# MCU1.net
KiCad netlist of a schematic drawn in Altium Designer
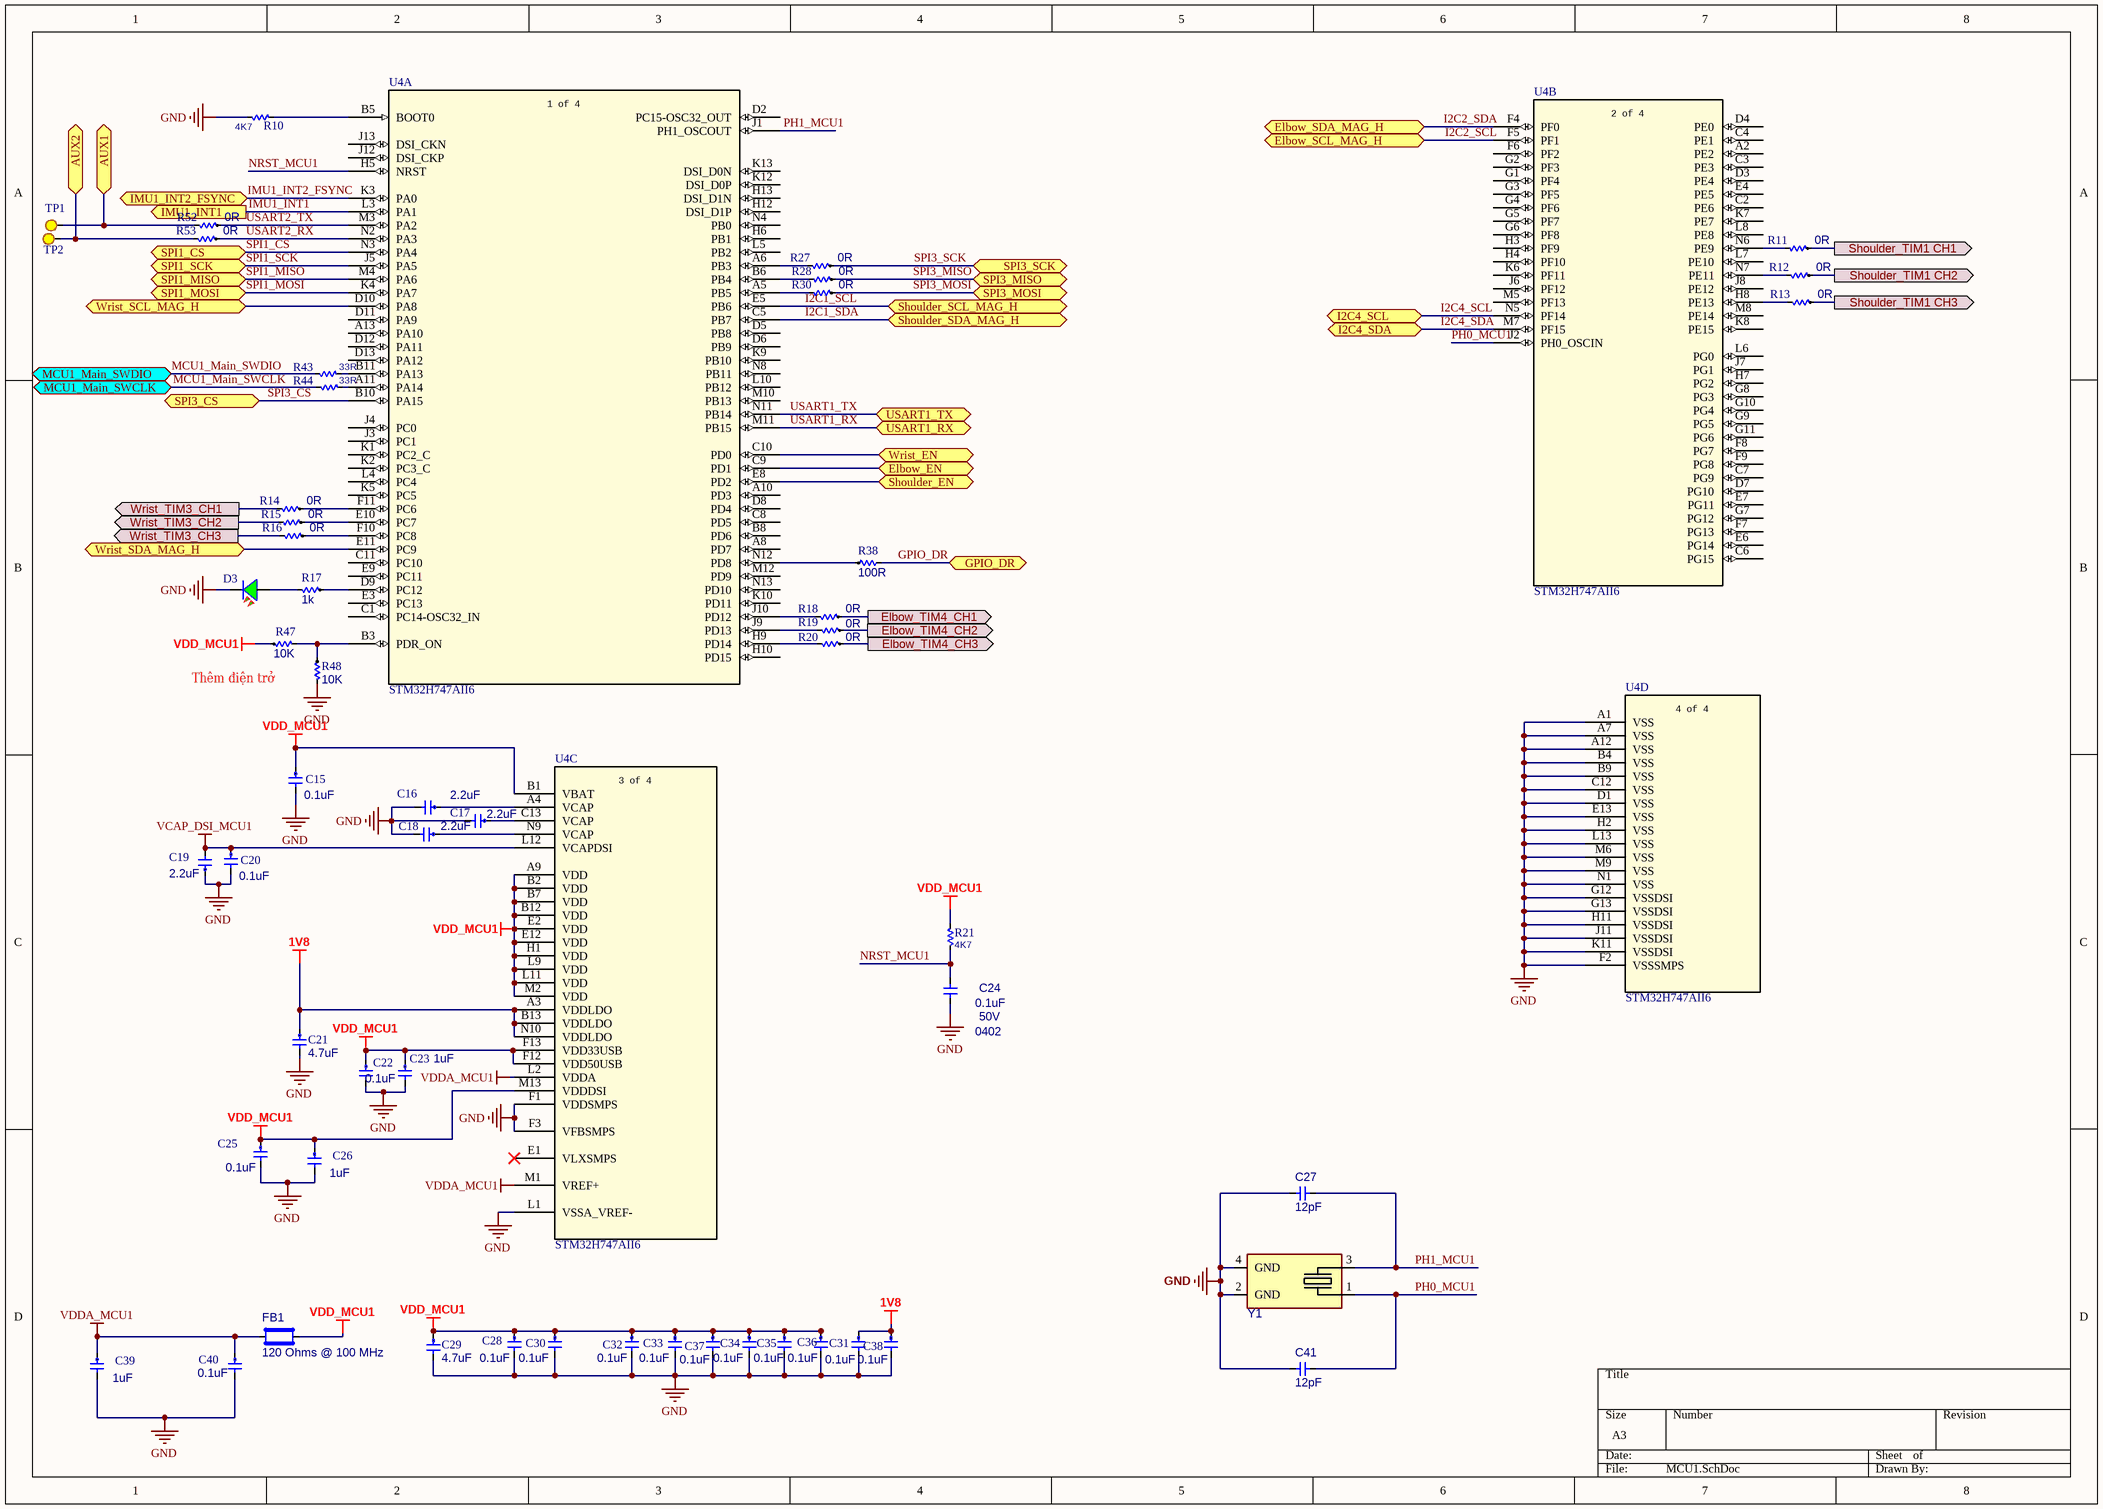
[diagram p0: MCU1.SchDoc]

(export (version "E")
  (design (tool "Eeschema 10.0.6"))
  (components
    (comp (ref "C15")
      (value "0.1uF")
      (footprint "CAP0402")
      (description "Cap 0.1uF 50V 0402")
      (fields (field (name "MP") "CC0402KRX5R9BB104") (field (name "TOLERANCE") "10%"))
      (libsource (lib "RTR (1)") (part "CAP0402 0.1uF 50V"))
    )
    (comp (ref "C16")
      (value "2.2uF")
      (footprint "CAP0402")
      (description "Cap 2.2uF 16V 0402")
      (fields (field (name "MP") "C1005X5R1C225K050BC") (field (name "VOLTAGE") "16V"))
      (libsource (lib "RTR (1)") (part "CAP0402 2.2uF 16V"))
    )
    (comp (ref "C17")
      (value "2.2uF")
      (footprint "CAP0402")
      (description "Cap 2.2uF 16V 0402")
      (fields (field (name "MP") "C1005X5R1C225K050BC") (field (name "VOLTAGE") "16V"))
      (libsource (lib "RTR (1)") (part "CAP0402 2.2uF 16V"))
    )
    (comp (ref "C18")
      (value "2.2uF")
      (footprint "CAP0402")
      (description "Cap 2.2uF 16V 0402")
      (fields (field (name "MP") "C1005X5R1C225K050BC") (field (name "VOLTAGE") "16V"))
      (libsource (lib "RTR (1)") (part "CAP0402 2.2uF 16V"))
    )
    (comp (ref "C19")
      (value "2.2uF")
      (footprint "CAP0402")
      (description "Cap 2.2uF 16V 0402")
      (fields (field (name "MP") "C1005X5R1C225K050BC") (field (name "VOLTAGE") "16V"))
      (libsource (lib "RTR (1)") (part "CAP0402 2.2uF 16V"))
    )
    (comp (ref "C20")
      (value "0.1uF")
      (footprint "CAP0402")
      (description "Cap 0.1uF 50V 0402")
      (fields (field (name "MP") "CC0402KRX5R9BB104") (field (name "TOLERANCE") "10%"))
      (libsource (lib "RTR (1)") (part "CAP0402 0.1uF 50V"))
    )
    (comp (ref "C21")
      (value "4.7uF")
      (footprint "CAP0402")
      (description "Cap 4.7uF 25V 0402")
      (fields (field (name "MP") "GRM155C61E475ME15J") (field (name "TOLERANCE") "20%"))
      (libsource (lib "RTR (1)") (part "CAP0402 4.7uF 25V"))
    )
    (comp (ref "C22")
      (value "1uF")
      (footprint "CAP0402")
      (description "Cap 1uF 50V 0402")
      (fields (field (name "MP") "GRM155R61H105KE05D") (field (name "Comment") "CAP0402 1uF 50V"))
      (libsource (lib "RTR (1)") (part "CAP0402 1uF 50V"))
    )
    (comp (ref "C23")
      (value "0.1uF")
      (footprint "CAP0402")
      (description "Cap 0.1uF 50V 0402")
      (fields (field (name "MP") "CC0402KRX5R9BB104") (field (name "TOLERANCE") "10%"))
      (libsource (lib "RTR (1)") (part "CAP0402 0.1uF 50V"))
    )
    (comp (ref "C24")
      (value "0.1uF")
      (footprint "CAP0402")
      (description "Cap 0.1uF 50V 0402")
      (fields
        (field (name "MP") "CC0402KRX5R9BB104")
        (field (name "VOLTAGE") "50V")
        (field (name "PACKAGE") "0402")
        (field (name "Comment") "CAP0402 0.1uF 50V")
      )
      (libsource (lib "RTR") (part "CAP0402 0.1uF 50V"))
    )
    (comp (ref "C25")
      (value "0.1uF")
      (footprint "CAP0402")
      (description "Cap 0.1uF 50V 0402")
      (fields (field (name "MP") "CC0402KRX5R9BB104") (field (name "TOLERANCE") "10%"))
      (libsource (lib "RTR (1)") (part "CAP0402 0.1uF 50V"))
    )
    (comp (ref "C26")
      (value "1uF")
      (footprint "CAP0402")
      (description "Cap 1uF 50V 0402")
      (fields (field (name "MP") "GRM155R61H105KE05D") (field (name "Comment") "CAP0402 1uF 50V"))
      (libsource (lib "RTR (1)") (part "CAP0402 1uF 50V"))
    )
    (comp (ref "C27")
      (value "12pF")
      (footprint "CAP0402")
      (description "Cap 12pF 50V 0402")
      (fields (field (name "Comment") "CAP0402 12pF 50V"))
      (libsource (lib "RTR") (part "CAP0402 12pF 50V"))
    )
    (comp (ref "C28")
      (value "0.1uF")
      (footprint "CAP0402")
      (description "Cap 0.1uF 50V 0402")
      (fields (field (name "MP") "CC0402KRX5R9BB104") (field (name "TOLERANCE") "10%"))
      (libsource (lib "RTR (1)") (part "CAP0402 0.1uF 50V"))
    )
    (comp (ref "C29")
      (value "4.7uF")
      (footprint "CAP0402")
      (description "Cap 4.7uF 25V 0402")
      (fields (field (name "MP") "GRM155C61E475ME15J") (field (name "TOLERANCE") "20%"))
      (libsource (lib "RTR (1)") (part "CAP0402 4.7uF 25V"))
    )
    (comp (ref "C30")
      (value "0.1uF")
      (footprint "CAP0402")
      (description "Cap 0.1uF 50V 0402")
      (fields (field (name "MP") "CC0402KRX5R9BB104") (field (name "TOLERANCE") "10%"))
      (libsource (lib "RTR (1)") (part "CAP0402 0.1uF 50V"))
    )
    (comp (ref "C31")
      (value "0.1uF")
      (footprint "CAP0402")
      (description "Cap 0.1uF 50V 0402")
      (fields (field (name "MP") "CC0402KRX5R9BB104") (field (name "TOLERANCE") "10%"))
      (libsource (lib "RTR (1)") (part "CAP0402 0.1uF 50V"))
    )
    (comp (ref "C32")
      (value "0.1uF")
      (footprint "CAP0402")
      (description "Cap 0.1uF 50V 0402")
      (fields (field (name "MP") "CC0402KRX5R9BB104") (field (name "TOLERANCE") "10%"))
      (libsource (lib "RTR (1)") (part "CAP0402 0.1uF 50V"))
    )
    (comp (ref "C33")
      (value "0.1uF")
      (footprint "CAP0402")
      (description "Cap 0.1uF 50V 0402")
      (fields (field (name "MP") "CC0402KRX5R9BB104") (field (name "TOLERANCE") "10%"))
      (libsource (lib "RTR (1)") (part "CAP0402 0.1uF 50V"))
    )
    (comp (ref "C34")
      (value "0.1uF")
      (footprint "CAP0402")
      (description "Cap 0.1uF 50V 0402")
      (fields (field (name "MP") "CC0402KRX5R9BB104") (field (name "TOLERANCE") "10%"))
      (libsource (lib "RTR (1)") (part "CAP0402 0.1uF 50V"))
    )
    (comp (ref "C35")
      (value "0.1uF")
      (footprint "CAP0402")
      (description "Cap 0.1uF 50V 0402")
      (fields (field (name "MP") "CC0402KRX5R9BB104") (field (name "TOLERANCE") "10%"))
      (libsource (lib "RTR (1)") (part "CAP0402 0.1uF 50V"))
    )
    (comp (ref "C36")
      (value "0.1uF")
      (footprint "CAP0402")
      (description "Cap 0.1uF 50V 0402")
      (fields (field (name "MP") "CC0402KRX5R9BB104") (field (name "TOLERANCE") "10%"))
      (libsource (lib "RTR (1)") (part "CAP0402 0.1uF 50V"))
    )
    (comp (ref "C37")
      (value "0.1uF")
      (footprint "CAP0402")
      (description "Cap 0.1uF 50V 0402")
      (fields (field (name "MP") "CC0402KRX5R9BB104") (field (name "TOLERANCE") "10%"))
      (libsource (lib "RTR (1)") (part "CAP0402 0.1uF 50V"))
    )
    (comp (ref "C38")
      (value "0.1uF")
      (footprint "CAP0402")
      (description "Cap 0.1uF 50V 0402")
      (fields (field (name "MP") "CC0402KRX5R9BB104") (field (name "TOLERANCE") "10%"))
      (libsource (lib "RTR (1)") (part "CAP0402 0.1uF 50V"))
    )
    (comp (ref "C39")
      (value "1uF")
      (footprint "CAP0402")
      (description "Cap 1uF 50V 0402")
      (fields (field (name "MP") "GRM155R61H105KE05D") (field (name "Comment") "CAP0402 1uF 50V"))
      (libsource (lib "RTR (1)") (part "CAP0402 1uF 50V"))
    )
    (comp (ref "C40")
      (value "0.1uF")
      (footprint "CAP0402")
      (description "Cap 0.1uF 50V 0402")
      (fields (field (name "MP") "CC0402KRX5R9BB104") (field (name "TOLERANCE") "10%"))
      (libsource (lib "RTR (1)") (part "CAP0402 0.1uF 50V"))
    )
    (comp (ref "C41")
      (value "12pF")
      (footprint "CAP0402")
      (description "Cap 12pF 50V 0402")
      (fields (field (name "Comment") "CAP0402 12pF 50V"))
      (libsource (lib "RTR") (part "CAP0402 12pF 50V"))
    )
    (comp (ref "D3")
      (value "SML-310MTT86")
      (footprint "LED0603 GREEN")
      (description "LED GREEN CLEAR 0603 SMD")
      (libsource (lib "HeraJetson_Modified") (part "CMP-01130-2"))
    )
    (comp (ref "FB1")
      (value "BLM15PX121SZ1D")
      (footprint "FERRIT0402")
      (description "120 Ohms @ 100 MHz 1 Power Line Ferrite Bead 0402 (1005 Metric) 2A 55mOhm")
      (fields (field (name "IMPEDANCE @ FREQUENCY") "120 Ohms @ 100 MHz"))
      (libsource (lib "RTR") (part "BLM15PX121SZ1D"))
    )
    (comp (ref "R10")
      (value "4K7")
      (footprint "RES0402")
      (description "RES 4K7 0402")
      (fields (field (name "MP") "RC0402JR-074K7L") (field (name "Comment") "RES0402 4K7"))
      (libsource (lib "RTR") (part "RES0402 4K7"))
    )
    (comp (ref "R11")
      (value "0R")
      (footprint "RES0402")
      (description "RES 0R 0402")
      (fields (field (name "MP") "RC0402JR-070RL") (field (name "TOLERANCE") "5%"))
      (libsource (lib "RTR (1)") (part "RES0402 0R"))
    )
    (comp (ref "R12")
      (value "0R")
      (footprint "RES0402")
      (description "RES 0R 0402")
      (fields (field (name "MP") "RC0402JR-070RL") (field (name "TOLERANCE") "5%"))
      (libsource (lib "RTR (1)") (part "RES0402 0R"))
    )
    (comp (ref "R13")
      (value "0R")
      (footprint "RES0402")
      (description "RES 0R 0402")
      (fields (field (name "MP") "RC0402JR-070RL") (field (name "TOLERANCE") "5%"))
      (libsource (lib "RTR (1)") (part "RES0402 0R"))
    )
    (comp (ref "R14")
      (value "0R")
      (footprint "RES0402")
      (description "RES 0R 0402")
      (fields (field (name "MP") "RC0402JR-070RL") (field (name "TOLERANCE") "5%"))
      (libsource (lib "RTR (1)") (part "RES0402 0R"))
    )
    (comp (ref "R15")
      (value "0R")
      (footprint "RES0402")
      (description "RES 0R 0402")
      (fields (field (name "MP") "RC0402JR-070RL") (field (name "TOLERANCE") "5%"))
      (libsource (lib "RTR (1)") (part "RES0402 0R"))
    )
    (comp (ref "R16")
      (value "0R")
      (footprint "RES0402")
      (description "RES 0R 0402")
      (fields (field (name "MP") "RC0402JR-070RL") (field (name "TOLERANCE") "5%"))
      (libsource (lib "RTR (1)") (part "RES0402 0R"))
    )
    (comp (ref "R17")
      (value "1k")
      (footprint "RES0402")
      (description "RES 1K 0402")
      (fields (field (name "MP") "RC0402FR-071KL") (field (name "TOLERANCE") "1%"))
      (libsource (lib "RTR (1)") (part "RES0402 1K"))
    )
    (comp (ref "R18")
      (value "0R")
      (footprint "RES0402")
      (description "RES 0R 0402")
      (fields (field (name "MP") "RC0402JR-070RL") (field (name "TOLERANCE") "5%"))
      (libsource (lib "RTR (1)") (part "RES0402 0R"))
    )
    (comp (ref "R19")
      (value "0R")
      (footprint "RES0402")
      (description "RES 0R 0402")
      (fields (field (name "MP") "RC0402JR-070RL") (field (name "TOLERANCE") "5%"))
      (libsource (lib "RTR (1)") (part "RES0402 0R"))
    )
    (comp (ref "R20")
      (value "0R")
      (footprint "RES0402")
      (description "RES 0R 0402")
      (fields (field (name "MP") "RC0402JR-070RL") (field (name "TOLERANCE") "5%"))
      (libsource (lib "RTR (1)") (part "RES0402 0R"))
    )
    (comp (ref "R21")
      (value "4K7")
      (footprint "RES0402")
      (description "RES 4K7 0402")
      (fields (field (name "MP") "RC0402JR-074K7L") (field (name "Comment") "RES0402 4K7"))
      (libsource (lib "RTR") (part "RES0402 4K7"))
    )
    (comp (ref "R27")
      (value "0R")
      (footprint "RES0402")
      (description "RES 0R 0402")
      (fields (field (name "MP") "RC0402JR-070RL") (field (name "TOLERANCE") "5%"))
      (libsource (lib "RTR (1)") (part "RES0402 0R"))
    )
    (comp (ref "R28")
      (value "0R")
      (footprint "RES0402")
      (description "RES 0R 0402")
      (fields (field (name "MP") "RC0402JR-070RL") (field (name "TOLERANCE") "5%"))
      (libsource (lib "RTR (1)") (part "RES0402 0R"))
    )
    (comp (ref "R30")
      (value "0R")
      (footprint "RES0402")
      (description "RES 0R 0402")
      (fields (field (name "MP") "RC0402JR-070RL") (field (name "TOLERANCE") "5%"))
      (libsource (lib "RTR (1)") (part "RES0402 0R"))
    )
    (comp (ref "R38")
      (value "100R")
      (footprint "RES0402")
      (description "RES 100R 0402")
      (fields (field (name "MP") "RC0402FR-07100RL") (field (name "Comment") "RES0402 100R"))
      (libsource (lib "RTR (1)") (part "RES0402 100R"))
    )
    (comp (ref "R43")
      (value "33R")
      (footprint "RES0402")
      (description "RES 33R 0402")
      (fields (field (name "MP") "RC0402FR-0733RL") (field (name "Comment") "RES0402 33R"))
      (libsource (lib "RTR (1)") (part "RES0402 33R"))
    )
    (comp (ref "R44")
      (value "33R")
      (footprint "RES0402")
      (description "RES 33R 0402")
      (fields (field (name "MP") "RC0402FR-0733RL") (field (name "Comment") "RES0402 33R"))
      (libsource (lib "RTR (1)") (part "RES0402 33R"))
    )
    (comp (ref "R47")
      (value "10K")
      (footprint "RES0402")
      (description "RES 10K 0402")
      (fields (field (name "MP") "RC0402FR-0710KL") (field (name "TOLERANCE") "1%"))
      (libsource (lib "RTR (1)") (part "RES0402 10K"))
    )
    (comp (ref "R48")
      (value "10K")
      (footprint "RES0402")
      (description "RES 10K 0402")
      (fields (field (name "MP") "RC0402FR-0710KL") (field (name "TOLERANCE") "1%"))
      (libsource (lib "RTR (1)") (part "RES0402 10K"))
    )
    (comp (ref "R52")
      (value "0R")
      (footprint "RES0402")
      (description "RES 0R 0402")
      (fields (field (name "MP") "RC0402JR-070RL") (field (name "TOLERANCE") "5%"))
      (libsource (lib "RTR (1)") (part "RES0402 0R"))
    )
    (comp (ref "R53")
      (value "0R")
      (footprint "RES0402")
      (description "RES 0R 0402")
      (fields (field (name "MP") "RC0402JR-070RL") (field (name "TOLERANCE") "5%"))
      (libsource (lib "RTR (1)") (part "RES0402 0R"))
    )
    (comp (ref "TP1")
      (value "Test Point")
      (footprint "Test Point")
      (libsource (lib "RTR (1)") (part "Test Point"))
    )
    (comp (ref "TP2")
      (value "Test Point")
      (footprint "Test Point")
      (libsource (lib "RTR (1)") (part "Test Point"))
    )
    (comp (ref "U4")
      (value "STM32H747AII6")
      (footprint "UFBGA169")
      (fields (field (name "COPYRIGHT") "Copyright (C) 2026 Ultra Librarian. All rights reserved."))
      (libsource (lib "RTR") (part "STM32H747AII6"))
    )
    (comp (ref "Y1")
      (value "ECS-240-12-37B-CKY-TR")
      (footprint "XTAL_ECS-240-12-37B-CKY-TR")
      (description "Crystal 24 MHz ±10ppm 12pF 50 Ohms 4-SMD, No Lead")
      (libsource (lib "RTR") (part "ECS-240-12-37B-CKY-TR"))
    )
  )
  (nets
    (net (code "1") (name "/AUX1") (class "Default")
      (node (ref "R52") (pin "1") (pinfunction "1_1") (pintype "passive"))
      (node (ref "TP1") (pin "TP") (pinfunction "Test_Point_TP") (pintype "passive"))
    )
    (net (code "2") (name "/AUX2") (class "Default")
      (node (ref "R53") (pin "1") (pinfunction "1_1") (pintype "passive"))
      (node (ref "TP2") (pin "TP") (pinfunction "Test_Point_TP") (pintype "passive"))
    )
    (net (code "3") (name "/Elbow_EN") (class "Default")
      (node (ref "U4") (pin "C9") (pinfunction "PD1_C9") (pintype "bidirectional"))
    )
    (net (code "4") (name "/Elbow_TIM4_CH1") (class "Default")
      (node (ref "R18") (pin "2") (pinfunction "2_2") (pintype "passive"))
    )
    (net (code "5") (name "/Elbow_TIM4_CH2") (class "Default")
      (node (ref "R19") (pin "2") (pinfunction "2_2") (pintype "passive"))
    )
    (net (code "6") (name "/Elbow_TIM4_CH3") (class "Default")
      (node (ref "R20") (pin "2") (pinfunction "2_2") (pintype "passive"))
    )
    (net (code "7") (name "/GPIO_DR") (class "Default")
      (node (ref "R38") (pin "1") (pinfunction "1_1") (pintype "passive"))
    )
    (net (code "8") (name "/I2C1_SCL") (class "Default")
      (node (ref "U4") (pin "E5") (pinfunction "PB6_E5") (pintype "bidirectional"))
    )
    (net (code "9") (name "/I2C1_SDA") (class "Default")
      (node (ref "U4") (pin "C5") (pinfunction "PB7_C5") (pintype "bidirectional"))
    )
    (net (code "10") (name "/I2C2_SCL") (class "Default")
      (node (ref "U4") (pin "F5") (pinfunction "PF1_F5") (pintype "bidirectional"))
    )
    (net (code "11") (name "/I2C2_SDA") (class "Default")
      (node (ref "U4") (pin "F4") (pinfunction "PF0_F4") (pintype "bidirectional"))
    )
    (net (code "12") (name "/I2C4_SCL") (class "Default")
      (node (ref "U4") (pin "N5") (pinfunction "PF14_N5") (pintype "bidirectional"))
    )
    (net (code "13") (name "/I2C4_SDA") (class "Default")
      (node (ref "U4") (pin "M7") (pinfunction "PF15_M7") (pintype "bidirectional"))
    )
    (net (code "14") (name "/IMU1_INT1") (class "Default")
      (node (ref "U4") (pin "L3") (pinfunction "PA1_L3") (pintype "bidirectional"))
    )
    (net (code "15") (name "/IMU1_INT2_FSYNC") (class "Default")
      (node (ref "U4") (pin "K3") (pinfunction "PA0_K3") (pintype "bidirectional"))
    )
    (net (code "16") (name "/MCU1_Main_SWCLK") (class "Default")
      (node (ref "R44") (pin "1") (pinfunction "1_1") (pintype "passive"))
    )
    (net (code "17") (name "/MCU1_Main_SWDIO") (class "Default")
      (node (ref "R43") (pin "1") (pinfunction "1_1") (pintype "passive"))
    )
    (net (code "18") (name "/NRST_MCU1") (class "Default")
      (node (ref "C24") (pin "2") (pinfunction "2_2") (pintype "passive"))
      (node (ref "R21") (pin "1") (pinfunction "1_1") (pintype "passive"))
      (node (ref "U4") (pin "H5") (pinfunction "NRST_H5") (pintype "bidirectional"))
    )
    (net (code "19") (name "/PH0_MCU1") (class "Default")
      (node (ref "C41") (pin "1") (pinfunction "1_1") (pintype "passive"))
      (node (ref "U4") (pin "J2") (pinfunction "PH0_OSCIN_J2") (pintype "bidirectional"))
      (node (ref "Y1") (pin "1") (pinfunction "IO_1") (pintype "passive"))
    )
    (net (code "20") (name "/PH1_MCU1") (class "Default")
      (node (ref "C27") (pin "1") (pinfunction "1_1") (pintype "passive"))
      (node (ref "U4") (pin "J1") (pinfunction "PH1_OSCOUT_J1") (pintype "bidirectional"))
      (node (ref "Y1") (pin "3") (pinfunction "IO_3") (pintype "passive"))
    )
    (net (code "21") (name "/SPI1_CS") (class "Default")
      (node (ref "U4") (pin "N3") (pinfunction "PA4_N3") (pintype "bidirectional"))
    )
    (net (code "22") (name "/SPI1_MISO") (class "Default")
      (node (ref "U4") (pin "M4") (pinfunction "PA6_M4") (pintype "bidirectional"))
    )
    (net (code "23") (name "/SPI1_MOSI") (class "Default")
      (node (ref "U4") (pin "K4") (pinfunction "PA7_K4") (pintype "bidirectional"))
    )
    (net (code "24") (name "/SPI1_SCK") (class "Default")
      (node (ref "U4") (pin "J5") (pinfunction "PA5_J5") (pintype "bidirectional"))
    )
    (net (code "25") (name "/SPI3_CS") (class "Default")
      (node (ref "U4") (pin "B10") (pinfunction "PA15_B10") (pintype "bidirectional"))
    )
    (net (code "26") (name "/SPI3_MISO") (class "Default")
      (node (ref "R28") (pin "2") (pinfunction "2_2") (pintype "passive"))
    )
    (net (code "27") (name "/SPI3_MOSI") (class "Default")
      (node (ref "R30") (pin "2") (pinfunction "2_2") (pintype "passive"))
    )
    (net (code "28") (name "/SPI3_SCK") (class "Default")
      (node (ref "R27") (pin "2") (pinfunction "2_2") (pintype "passive"))
    )
    (net (code "29") (name "/Shoulder_EN") (class "Default")
      (node (ref "U4") (pin "E8") (pinfunction "PD2_E8") (pintype "bidirectional"))
    )
    (net (code "30") (name "/Shoulder_TIM1 CH1") (class "Default")
      (node (ref "R11") (pin "2") (pinfunction "2_2") (pintype "passive"))
    )
    (net (code "31") (name "/Shoulder_TIM1 CH2") (class "Default")
      (node (ref "R12") (pin "2") (pinfunction "2_2") (pintype "passive"))
    )
    (net (code "32") (name "/Shoulder_TIM1 CH3") (class "Default")
      (node (ref "R13") (pin "2") (pinfunction "2_2") (pintype "passive"))
    )
    (net (code "33") (name "/USART1_RX") (class "Default")
      (node (ref "U4") (pin "M11") (pinfunction "PB15_M11") (pintype "bidirectional"))
    )
    (net (code "34") (name "/USART1_TX") (class "Default")
      (node (ref "U4") (pin "N11") (pinfunction "PB14_N11") (pintype "bidirectional"))
    )
    (net (code "35") (name "/USART2_RX") (class "Default")
      (node (ref "R53") (pin "2") (pinfunction "2_2") (pintype "passive"))
      (node (ref "U4") (pin "N2") (pinfunction "PA3_N2") (pintype "bidirectional"))
    )
    (net (code "36") (name "/USART2_TX") (class "Default")
      (node (ref "R52") (pin "2") (pinfunction "2_2") (pintype "passive"))
      (node (ref "U4") (pin "M3") (pinfunction "PA2_M3") (pintype "bidirectional"))
    )
    (net (code "37") (name "/Wrist_EN") (class "Default")
      (node (ref "U4") (pin "C10") (pinfunction "PD0_C10") (pintype "bidirectional"))
    )
    (net (code "38") (name "/Wrist_SCL_MAG_H") (class "Default")
      (node (ref "U4") (pin "D10") (pinfunction "PA8_D10") (pintype "bidirectional"))
    )
    (net (code "39") (name "/Wrist_SDA_MAG_H") (class "Default")
      (node (ref "U4") (pin "E11") (pinfunction "PC9_E11") (pintype "bidirectional"))
    )
    (net (code "40") (name "/Wrist_TIM3_CH1") (class "Default")
      (node (ref "R14") (pin "1") (pinfunction "1_1") (pintype "passive"))
    )
    (net (code "41") (name "/Wrist_TIM3_CH2") (class "Default")
      (node (ref "R15") (pin "1") (pinfunction "1_1") (pintype "passive"))
    )
    (net (code "42") (name "/Wrist_TIM3_CH3") (class "Default")
      (node (ref "R16") (pin "1") (pinfunction "1_1") (pintype "passive"))
    )
    (net (code "43") (name "1V8") (class "Default")
      (node (ref "C21") (pin "1") (pinfunction "1_1") (pintype "passive"))
      (node (ref "C31") (pin "1") (pinfunction "1_1") (pintype "passive"))
      (node (ref "C38") (pin "1") (pinfunction "1_1") (pintype "passive"))
      (node (ref "U4") (pin "A3") (pinfunction "VDDLDO_A3") (pintype "power_in"))
      (node (ref "U4") (pin "B13") (pinfunction "VDDLDO_B13") (pintype "power_in"))
      (node (ref "U4") (pin "N10") (pinfunction "VDDLDO_N10") (pintype "power_in"))
    )
    (net (code "44") (name "GND") (class "Default")
      (node (ref "C15") (pin "2") (pinfunction "2_2") (pintype "passive"))
      (node (ref "C16") (pin "2") (pinfunction "2_2") (pintype "passive"))
      (node (ref "C17") (pin "2") (pinfunction "2_2") (pintype "passive"))
      (node (ref "C18") (pin "2") (pinfunction "2_2") (pintype "passive"))
      (node (ref "C19") (pin "1") (pinfunction "1_1") (pintype "passive"))
      (node (ref "C20") (pin "2") (pinfunction "2_2") (pintype "passive"))
      (node (ref "C21") (pin "2") (pinfunction "2_2") (pintype "passive"))
      (node (ref "C22") (pin "2") (pinfunction "2_2") (pintype "passive"))
      (node (ref "C23") (pin "2") (pinfunction "2_2") (pintype "passive"))
      (node (ref "C24") (pin "1") (pinfunction "1_1") (pintype "passive"))
      (node (ref "C25") (pin "2") (pinfunction "2_2") (pintype "passive"))
      (node (ref "C26") (pin "2") (pinfunction "2_2") (pintype "passive"))
      (node (ref "C27") (pin "2") (pinfunction "2_2") (pintype "passive"))
      (node (ref "C28") (pin "2") (pinfunction "2_2") (pintype "passive"))
      (node (ref "C29") (pin "2") (pinfunction "2_2") (pintype "passive"))
      (node (ref "C30") (pin "2") (pinfunction "2_2") (pintype "passive"))
      (node (ref "C31") (pin "2") (pinfunction "2_2") (pintype "passive"))
      (node (ref "C32") (pin "2") (pinfunction "2_2") (pintype "passive"))
      (node (ref "C33") (pin "2") (pinfunction "2_2") (pintype "passive"))
      (node (ref "C34") (pin "2") (pinfunction "2_2") (pintype "passive"))
      (node (ref "C35") (pin "2") (pinfunction "2_2") (pintype "passive"))
      (node (ref "C36") (pin "2") (pinfunction "2_2") (pintype "passive"))
      (node (ref "C37") (pin "2") (pinfunction "2_2") (pintype "passive"))
      (node (ref "C38") (pin "2") (pinfunction "2_2") (pintype "passive"))
      (node (ref "C39") (pin "2") (pinfunction "2_2") (pintype "passive"))
      (node (ref "C40") (pin "2") (pinfunction "2_2") (pintype "passive"))
      (node (ref "C41") (pin "2") (pinfunction "2_2") (pintype "passive"))
      (node (ref "D3") (pin "1") (pinfunction "1_1") (pintype "passive"))
      (node (ref "R10") (pin "1") (pinfunction "1_1") (pintype "passive"))
      (node (ref "R48") (pin "1") (pinfunction "1_1") (pintype "passive"))
      (node (ref "U4") (pin "A1") (pinfunction "VSS_A1") (pintype "power_in"))
      (node (ref "U4") (pin "A12") (pinfunction "VSS_A12") (pintype "power_in"))
      (node (ref "U4") (pin "A7") (pinfunction "VSS_A7") (pintype "power_in"))
      (node (ref "U4") (pin "B4") (pinfunction "VSS_B4") (pintype "power_in"))
      (node (ref "U4") (pin "B9") (pinfunction "VSS_B9") (pintype "power_in"))
      (node (ref "U4") (pin "C12") (pinfunction "VSS_C12") (pintype "power_in"))
      (node (ref "U4") (pin "D1") (pinfunction "VSS_D1") (pintype "power_in"))
      (node (ref "U4") (pin "E13") (pinfunction "VSS_E13") (pintype "power_in"))
      (node (ref "U4") (pin "F1") (pinfunction "VDDSMPS_F1") (pintype "power_in"))
      (node (ref "U4") (pin "F2") (pinfunction "VSSSMPS_F2") (pintype "power_in"))
      (node (ref "U4") (pin "F3") (pinfunction "VFBSMPS_F3") (pintype "power_in"))
      (node (ref "U4") (pin "G12") (pinfunction "VSSDSI_G12") (pintype "power_in"))
      (node (ref "U4") (pin "G13") (pinfunction "VSSDSI_G13") (pintype "power_in"))
      (node (ref "U4") (pin "H11") (pinfunction "VSSDSI_H11") (pintype "power_in"))
      (node (ref "U4") (pin "H2") (pinfunction "VSS_H2") (pintype "power_in"))
      (node (ref "U4") (pin "J11") (pinfunction "VSSDSI_J11") (pintype "power_in"))
      (node (ref "U4") (pin "K11") (pinfunction "VSSDSI_K11") (pintype "power_in"))
      (node (ref "U4") (pin "L1") (pinfunction "VSSA_VREF-_L1") (pintype "power_in"))
      (node (ref "U4") (pin "L13") (pinfunction "VSS_L13") (pintype "power_in"))
      (node (ref "U4") (pin "M6") (pinfunction "VSS_M6") (pintype "power_in"))
      (node (ref "U4") (pin "M9") (pinfunction "VSS_M9") (pintype "power_in"))
      (node (ref "U4") (pin "N1") (pinfunction "VSS_N1") (pintype "power_in"))
      (node (ref "Y1") (pin "2") (pinfunction "GND_2") (pintype "passive"))
      (node (ref "Y1") (pin "4") (pinfunction "GND_4") (pintype "passive"))
    )
    (net (code "45") (name "Net-(C16-Pad1)") (class "Default")
      (node (ref "C16") (pin "1") (pinfunction "1_1") (pintype "passive"))
      (node (ref "U4") (pin "A4") (pinfunction "VCAP_A4") (pintype "power_in"))
    )
    (net (code "46") (name "Net-(C17-Pad1)") (class "Default")
      (node (ref "C17") (pin "1") (pinfunction "1_1") (pintype "passive"))
      (node (ref "U4") (pin "C13") (pinfunction "VCAP_C13") (pintype "power_in"))
    )
    (net (code "47") (name "Net-(C18-Pad1)") (class "Default")
      (node (ref "C18") (pin "1") (pinfunction "1_1") (pintype "passive"))
      (node (ref "U4") (pin "N9") (pinfunction "VCAP_N9") (pintype "power_in"))
    )
    (net (code "48") (name "Net-(D3-Pad2)") (class "Default")
      (node (ref "D3") (pin "2") (pinfunction "2_2") (pintype "passive"))
      (node (ref "R17") (pin "1") (pinfunction "1_1") (pintype "passive"))
    )
    (net (code "49") (name "Net-(U4A-BOOT0)") (class "Default")
      (node (ref "R10") (pin "2") (pinfunction "2_2") (pintype "passive"))
      (node (ref "U4") (pin "B5") (pinfunction "BOOT0_B5") (pintype "input"))
    )
    (net (code "50") (name "Net-(U4A-PA13)") (class "Default")
      (node (ref "R43") (pin "2") (pinfunction "2_2") (pintype "passive"))
      (node (ref "U4") (pin "B11") (pinfunction "PA13_B11") (pintype "bidirectional"))
    )
    (net (code "51") (name "Net-(U4A-PA14)") (class "Default")
      (node (ref "R44") (pin "2") (pinfunction "2_2") (pintype "passive"))
      (node (ref "U4") (pin "A11") (pinfunction "PA14_A11") (pintype "bidirectional"))
    )
    (net (code "52") (name "Net-(U4A-PB3)") (class "Default")
      (node (ref "R27") (pin "1") (pinfunction "1_1") (pintype "passive"))
      (node (ref "U4") (pin "A6") (pinfunction "PB3_A6") (pintype "bidirectional"))
    )
    (net (code "53") (name "Net-(U4A-PB4)") (class "Default")
      (node (ref "R28") (pin "1") (pinfunction "1_1") (pintype "passive"))
      (node (ref "U4") (pin "B6") (pinfunction "PB4_B6") (pintype "bidirectional"))
    )
    (net (code "54") (name "Net-(U4A-PB5)") (class "Default")
      (node (ref "R30") (pin "1") (pinfunction "1_1") (pintype "passive"))
      (node (ref "U4") (pin "A5") (pinfunction "PB5_A5") (pintype "bidirectional"))
    )
    (net (code "55") (name "Net-(U4A-PC6)") (class "Default")
      (node (ref "R14") (pin "2") (pinfunction "2_2") (pintype "passive"))
      (node (ref "U4") (pin "F11") (pinfunction "PC6_F11") (pintype "bidirectional"))
    )
    (net (code "56") (name "Net-(U4A-PC7)") (class "Default")
      (node (ref "R15") (pin "2") (pinfunction "2_2") (pintype "passive"))
      (node (ref "U4") (pin "E10") (pinfunction "PC7_E10") (pintype "bidirectional"))
    )
    (net (code "57") (name "Net-(U4A-PC8)") (class "Default")
      (node (ref "R16") (pin "2") (pinfunction "2_2") (pintype "passive"))
      (node (ref "U4") (pin "F10") (pinfunction "PC8_F10") (pintype "bidirectional"))
    )
    (net (code "58") (name "Net-(U4A-PC12)") (class "Default")
      (node (ref "R17") (pin "2") (pinfunction "2_2") (pintype "passive"))
      (node (ref "U4") (pin "D9") (pinfunction "PC12_D9") (pintype "bidirectional"))
    )
    (net (code "59") (name "Net-(U4A-PD8)") (class "Default")
      (node (ref "R38") (pin "2") (pinfunction "2_2") (pintype "passive"))
      (node (ref "U4") (pin "N12") (pinfunction "PD8_N12") (pintype "bidirectional"))
    )
    (net (code "60") (name "Net-(U4A-PD12)") (class "Default")
      (node (ref "R18") (pin "1") (pinfunction "1_1") (pintype "passive"))
      (node (ref "U4") (pin "J10") (pinfunction "PD12_J10") (pintype "bidirectional"))
    )
    (net (code "61") (name "Net-(U4A-PD13)") (class "Default")
      (node (ref "R19") (pin "1") (pinfunction "1_1") (pintype "passive"))
      (node (ref "U4") (pin "J9") (pinfunction "PD13_J9") (pintype "bidirectional"))
    )
    (net (code "62") (name "Net-(U4A-PD14)") (class "Default")
      (node (ref "R20") (pin "1") (pinfunction "1_1") (pintype "passive"))
      (node (ref "U4") (pin "H9") (pinfunction "PD14_H9") (pintype "bidirectional"))
    )
    (net (code "63") (name "Net-(U4A-PDR_ON)") (class "Default")
      (node (ref "R47") (pin "1") (pinfunction "1_1") (pintype "passive"))
      (node (ref "R48") (pin "2") (pinfunction "2_2") (pintype "passive"))
      (node (ref "U4") (pin "B3") (pinfunction "PDR_ON_B3") (pintype "bidirectional"))
    )
    (net (code "64") (name "Net-(U4B-PE9)") (class "Default")
      (node (ref "R11") (pin "1") (pinfunction "1_1") (pintype "passive"))
      (node (ref "U4") (pin "N6") (pinfunction "PE9_N6") (pintype "bidirectional"))
    )
    (net (code "65") (name "Net-(U4B-PE11)") (class "Default")
      (node (ref "R12") (pin "1") (pinfunction "1_1") (pintype "passive"))
      (node (ref "U4") (pin "N7") (pinfunction "PE11_N7") (pintype "bidirectional"))
    )
    (net (code "66") (name "Net-(U4B-PE13)") (class "Default")
      (node (ref "R13") (pin "1") (pinfunction "1_1") (pintype "passive"))
      (node (ref "U4") (pin "H8") (pinfunction "PE13_H8") (pintype "bidirectional"))
    )
    (net (code "67") (name "VCAP_DSI_MCU1") (class "Default")
      (node (ref "C19") (pin "2") (pinfunction "2_2") (pintype "passive"))
      (node (ref "C20") (pin "1") (pinfunction "1_1") (pintype "passive"))
      (node (ref "U4") (pin "L12") (pinfunction "VCAPDSI_L12") (pintype "power_in"))
    )
    (net (code "68") (name "VDDA_MCU1") (class "Default")
      (node (ref "C39") (pin "1") (pinfunction "1_1") (pintype "passive"))
      (node (ref "C40") (pin "1") (pinfunction "1_1") (pintype "passive"))
      (node (ref "FB1") (pin "1") (pinfunction "1_1") (pintype "passive"))
      (node (ref "U4") (pin "L2") (pinfunction "VDDA_L2") (pintype "power_in"))
      (node (ref "U4") (pin "M1") (pinfunction "VREF+_M1") (pintype "power_in"))
    )
    (net (code "69") (name "VDD_MCU1") (class "Default")
      (node (ref "C15") (pin "1") (pinfunction "1_1") (pintype "passive"))
      (node (ref "C22") (pin "1") (pinfunction "1_1") (pintype "passive"))
      (node (ref "C23") (pin "1") (pinfunction "1_1") (pintype "passive"))
      (node (ref "C25") (pin "1") (pinfunction "1_1") (pintype "passive"))
      (node (ref "C26") (pin "1") (pinfunction "1_1") (pintype "passive"))
      (node (ref "C28") (pin "1") (pinfunction "1_1") (pintype "passive"))
      (node (ref "C29") (pin "1") (pinfunction "1_1") (pintype "passive"))
      (node (ref "C30") (pin "1") (pinfunction "1_1") (pintype "passive"))
      (node (ref "C32") (pin "1") (pinfunction "1_1") (pintype "passive"))
      (node (ref "C33") (pin "1") (pinfunction "1_1") (pintype "passive"))
      (node (ref "C34") (pin "1") (pinfunction "1_1") (pintype "passive"))
      (node (ref "C35") (pin "1") (pinfunction "1_1") (pintype "passive"))
      (node (ref "C36") (pin "1") (pinfunction "1_1") (pintype "passive"))
      (node (ref "C37") (pin "1") (pinfunction "1_1") (pintype "passive"))
      (node (ref "FB1") (pin "2") (pinfunction "2_2") (pintype "passive"))
      (node (ref "R21") (pin "2") (pinfunction "2_2") (pintype "passive"))
      (node (ref "R47") (pin "2") (pinfunction "2_2") (pintype "passive"))
      (node (ref "U4") (pin "A9") (pinfunction "VDD_A9") (pintype "power_in"))
      (node (ref "U4") (pin "B1") (pinfunction "VBAT_B1") (pintype "power_in"))
      (node (ref "U4") (pin "B12") (pinfunction "VDD_B12") (pintype "power_in"))
      (node (ref "U4") (pin "B2") (pinfunction "VDD_B2") (pintype "power_in"))
      (node (ref "U4") (pin "B7") (pinfunction "VDD_B7") (pintype "power_in"))
      (node (ref "U4") (pin "E12") (pinfunction "VDD_E12") (pintype "power_in"))
      (node (ref "U4") (pin "E2") (pinfunction "VDD_E2") (pintype "power_in"))
      (node (ref "U4") (pin "F12") (pinfunction "VDD50USB_F12") (pintype "power_in"))
      (node (ref "U4") (pin "F13") (pinfunction "VDD33USB_F13") (pintype "power_in"))
      (node (ref "U4") (pin "H1") (pinfunction "VDD_H1") (pintype "power_in"))
      (node (ref "U4") (pin "L11") (pinfunction "VDD_L11") (pintype "power_in"))
      (node (ref "U4") (pin "L9") (pinfunction "VDD_L9") (pintype "power_in"))
      (node (ref "U4") (pin "M13") (pinfunction "VDDDSI_M13") (pintype "power_in"))
      (node (ref "U4") (pin "M2") (pinfunction "VDD_M2") (pintype "power_in"))
    )
    (net (code "70") (name "unconnected-(U4A-DSI_CKN-PadJ13)") (class "Default")
      (node (ref "U4") (pin "J13") (pinfunction "DSI_CKN_J13") (pintype "bidirectional"))
    )
    (net (code "71") (name "unconnected-(U4A-DSI_CKP-PadJ12)") (class "Default")
      (node (ref "U4") (pin "J12") (pinfunction "DSI_CKP_J12") (pintype "bidirectional"))
    )
    (net (code "72") (name "unconnected-(U4A-DSI_D0N-PadK13)") (class "Default")
      (node (ref "U4") (pin "K13") (pinfunction "DSI_D0N_K13") (pintype "bidirectional"))
    )
    (net (code "73") (name "unconnected-(U4A-DSI_D0P-PadK12)") (class "Default")
      (node (ref "U4") (pin "K12") (pinfunction "DSI_D0P_K12") (pintype "bidirectional"))
    )
    (net (code "74") (name "unconnected-(U4A-DSI_D1N-PadH13)") (class "Default")
      (node (ref "U4") (pin "H13") (pinfunction "DSI_D1N_H13") (pintype "bidirectional"))
    )
    (net (code "75") (name "unconnected-(U4A-DSI_D1P-PadH12)") (class "Default")
      (node (ref "U4") (pin "H12") (pinfunction "DSI_D1P_H12") (pintype "bidirectional"))
    )
    (net (code "76") (name "unconnected-(U4A-PA9-PadD11)") (class "Default")
      (node (ref "U4") (pin "D11") (pinfunction "PA9_D11") (pintype "bidirectional"))
    )
    (net (code "77") (name "unconnected-(U4A-PA10-PadA13)") (class "Default")
      (node (ref "U4") (pin "A13") (pinfunction "PA10_A13") (pintype "bidirectional"))
    )
    (net (code "78") (name "unconnected-(U4A-PA11-PadD12)") (class "Default")
      (node (ref "U4") (pin "D12") (pinfunction "PA11_D12") (pintype "bidirectional"))
    )
    (net (code "79") (name "unconnected-(U4A-PA12-PadD13)") (class "Default")
      (node (ref "U4") (pin "D13") (pinfunction "PA12_D13") (pintype "bidirectional"))
    )
    (net (code "80") (name "unconnected-(U4A-PB0-PadN4)") (class "Default")
      (node (ref "U4") (pin "N4") (pinfunction "PB0_N4") (pintype "bidirectional"))
    )
    (net (code "81") (name "unconnected-(U4A-PB1-PadH6)") (class "Default")
      (node (ref "U4") (pin "H6") (pinfunction "PB1_H6") (pintype "bidirectional"))
    )
    (net (code "82") (name "unconnected-(U4A-PB2-PadL5)") (class "Default")
      (node (ref "U4") (pin "L5") (pinfunction "PB2_L5") (pintype "bidirectional"))
    )
    (net (code "83") (name "unconnected-(U4A-PB8-PadD5)") (class "Default")
      (node (ref "U4") (pin "D5") (pinfunction "PB8_D5") (pintype "bidirectional"))
    )
    (net (code "84") (name "unconnected-(U4A-PB9-PadD6)") (class "Default")
      (node (ref "U4") (pin "D6") (pinfunction "PB9_D6") (pintype "bidirectional"))
    )
    (net (code "85") (name "unconnected-(U4A-PB10-PadK9)") (class "Default")
      (node (ref "U4") (pin "K9") (pinfunction "PB10_K9") (pintype "bidirectional"))
    )
    (net (code "86") (name "unconnected-(U4A-PB11-PadN8)") (class "Default")
      (node (ref "U4") (pin "N8") (pinfunction "PB11_N8") (pintype "bidirectional"))
    )
    (net (code "87") (name "unconnected-(U4A-PB12-PadL10)") (class "Default")
      (node (ref "U4") (pin "L10") (pinfunction "PB12_L10") (pintype "bidirectional"))
    )
    (net (code "88") (name "unconnected-(U4A-PB13-PadM10)") (class "Default")
      (node (ref "U4") (pin "M10") (pinfunction "PB13_M10") (pintype "bidirectional"))
    )
    (net (code "89") (name "unconnected-(U4A-PC0-PadJ4)") (class "Default")
      (node (ref "U4") (pin "J4") (pinfunction "PC0_J4") (pintype "bidirectional"))
    )
    (net (code "90") (name "unconnected-(U4A-PC1-PadJ3)") (class "Default")
      (node (ref "U4") (pin "J3") (pinfunction "PC1_J3") (pintype "bidirectional"))
    )
    (net (code "91") (name "unconnected-(U4A-PC2_C-PadK1)") (class "Default")
      (node (ref "U4") (pin "K1") (pinfunction "PC2_C_K1") (pintype "bidirectional"))
    )
    (net (code "92") (name "unconnected-(U4A-PC3_C-PadK2)") (class "Default")
      (node (ref "U4") (pin "K2") (pinfunction "PC3_C_K2") (pintype "bidirectional"))
    )
    (net (code "93") (name "unconnected-(U4A-PC4-PadL4)") (class "Default")
      (node (ref "U4") (pin "L4") (pinfunction "PC4_L4") (pintype "bidirectional"))
    )
    (net (code "94") (name "unconnected-(U4A-PC5-PadK5)") (class "Default")
      (node (ref "U4") (pin "K5") (pinfunction "PC5_K5") (pintype "bidirectional"))
    )
    (net (code "95") (name "unconnected-(U4A-PC10-PadC11)") (class "Default")
      (node (ref "U4") (pin "C11") (pinfunction "PC10_C11") (pintype "bidirectional"))
    )
    (net (code "96") (name "unconnected-(U4A-PC11-PadE9)") (class "Default")
      (node (ref "U4") (pin "E9") (pinfunction "PC11_E9") (pintype "bidirectional"))
    )
    (net (code "97") (name "unconnected-(U4A-PC13-PadE3)") (class "Default")
      (node (ref "U4") (pin "E3") (pinfunction "PC13_E3") (pintype "bidirectional"))
    )
    (net (code "98") (name "unconnected-(U4A-PC14-OSC32_IN-PadC1)") (class "Default")
      (node (ref "U4") (pin "C1") (pinfunction "PC14-OSC32_IN_C1") (pintype "bidirectional"))
    )
    (net (code "99") (name "unconnected-(U4A-PC15-OSC32_OUT-PadD2)") (class "Default")
      (node (ref "U4") (pin "D2") (pinfunction "PC15-OSC32_OUT_D2") (pintype "bidirectional"))
    )
    (net (code "100") (name "unconnected-(U4A-PD3-PadA10)") (class "Default")
      (node (ref "U4") (pin "A10") (pinfunction "PD3_A10") (pintype "bidirectional"))
    )
    (net (code "101") (name "unconnected-(U4A-PD4-PadD8)") (class "Default")
      (node (ref "U4") (pin "D8") (pinfunction "PD4_D8") (pintype "bidirectional"))
    )
    (net (code "102") (name "unconnected-(U4A-PD5-PadC8)") (class "Default")
      (node (ref "U4") (pin "C8") (pinfunction "PD5_C8") (pintype "bidirectional"))
    )
    (net (code "103") (name "unconnected-(U4A-PD6-PadB8)") (class "Default")
      (node (ref "U4") (pin "B8") (pinfunction "PD6_B8") (pintype "bidirectional"))
    )
    (net (code "104") (name "unconnected-(U4A-PD7-PadA8)") (class "Default")
      (node (ref "U4") (pin "A8") (pinfunction "PD7_A8") (pintype "bidirectional"))
    )
    (net (code "105") (name "unconnected-(U4A-PD9-PadM12)") (class "Default")
      (node (ref "U4") (pin "M12") (pinfunction "PD9_M12") (pintype "bidirectional"))
    )
    (net (code "106") (name "unconnected-(U4A-PD10-PadN13)") (class "Default")
      (node (ref "U4") (pin "N13") (pinfunction "PD10_N13") (pintype "bidirectional"))
    )
    (net (code "107") (name "unconnected-(U4A-PD11-PadK10)") (class "Default")
      (node (ref "U4") (pin "K10") (pinfunction "PD11_K10") (pintype "bidirectional"))
    )
    (net (code "108") (name "unconnected-(U4A-PD15-PadH10)") (class "Default")
      (node (ref "U4") (pin "H10") (pinfunction "PD15_H10") (pintype "bidirectional"))
    )
    (net (code "109") (name "unconnected-(U4B-PE0-PadD4)") (class "Default")
      (node (ref "U4") (pin "D4") (pinfunction "PE0_D4") (pintype "bidirectional"))
    )
    (net (code "110") (name "unconnected-(U4B-PE1-PadC4)") (class "Default")
      (node (ref "U4") (pin "C4") (pinfunction "PE1_C4") (pintype "bidirectional"))
    )
    (net (code "111") (name "unconnected-(U4B-PE2-PadA2)") (class "Default")
      (node (ref "U4") (pin "A2") (pinfunction "PE2_A2") (pintype "bidirectional"))
    )
    (net (code "112") (name "unconnected-(U4B-PE3-PadC3)") (class "Default")
      (node (ref "U4") (pin "C3") (pinfunction "PE3_C3") (pintype "bidirectional"))
    )
    (net (code "113") (name "unconnected-(U4B-PE4-PadD3)") (class "Default")
      (node (ref "U4") (pin "D3") (pinfunction "PE4_D3") (pintype "bidirectional"))
    )
    (net (code "114") (name "unconnected-(U4B-PE5-PadE4)") (class "Default")
      (node (ref "U4") (pin "E4") (pinfunction "PE5_E4") (pintype "bidirectional"))
    )
    (net (code "115") (name "unconnected-(U4B-PE6-PadC2)") (class "Default")
      (node (ref "U4") (pin "C2") (pinfunction "PE6_C2") (pintype "bidirectional"))
    )
    (net (code "116") (name "unconnected-(U4B-PE7-PadK7)") (class "Default")
      (node (ref "U4") (pin "K7") (pinfunction "PE7_K7") (pintype "bidirectional"))
    )
    (net (code "117") (name "unconnected-(U4B-PE8-PadL8)") (class "Default")
      (node (ref "U4") (pin "L8") (pinfunction "PE8_L8") (pintype "bidirectional"))
    )
    (net (code "118") (name "unconnected-(U4B-PE10-PadL7)") (class "Default")
      (node (ref "U4") (pin "L7") (pinfunction "PE10_L7") (pintype "bidirectional"))
    )
    (net (code "119") (name "unconnected-(U4B-PE12-PadJ8)") (class "Default")
      (node (ref "U4") (pin "J8") (pinfunction "PE12_J8") (pintype "bidirectional"))
    )
    (net (code "120") (name "unconnected-(U4B-PE14-PadM8)") (class "Default")
      (node (ref "U4") (pin "M8") (pinfunction "PE14_M8") (pintype "bidirectional"))
    )
    (net (code "121") (name "unconnected-(U4B-PE15-PadK8)") (class "Default")
      (node (ref "U4") (pin "K8") (pinfunction "PE15_K8") (pintype "bidirectional"))
    )
    (net (code "122") (name "unconnected-(U4B-PF2-PadF6)") (class "Default")
      (node (ref "U4") (pin "F6") (pinfunction "PF2_F6") (pintype "bidirectional"))
    )
    (net (code "123") (name "unconnected-(U4B-PF3-PadG2)") (class "Default")
      (node (ref "U4") (pin "G2") (pinfunction "PF3_G2") (pintype "bidirectional"))
    )
    (net (code "124") (name "unconnected-(U4B-PF4-PadG1)") (class "Default")
      (node (ref "U4") (pin "G1") (pinfunction "PF4_G1") (pintype "bidirectional"))
    )
    (net (code "125") (name "unconnected-(U4B-PF5-PadG3)") (class "Default")
      (node (ref "U4") (pin "G3") (pinfunction "PF5_G3") (pintype "bidirectional"))
    )
    (net (code "126") (name "unconnected-(U4B-PF6-PadG4)") (class "Default")
      (node (ref "U4") (pin "G4") (pinfunction "PF6_G4") (pintype "bidirectional"))
    )
    (net (code "127") (name "unconnected-(U4B-PF7-PadG5)") (class "Default")
      (node (ref "U4") (pin "G5") (pinfunction "PF7_G5") (pintype "bidirectional"))
    )
    (net (code "128") (name "unconnected-(U4B-PF8-PadG6)") (class "Default")
      (node (ref "U4") (pin "G6") (pinfunction "PF8_G6") (pintype "bidirectional"))
    )
    (net (code "129") (name "unconnected-(U4B-PF9-PadH3)") (class "Default")
      (node (ref "U4") (pin "H3") (pinfunction "PF9_H3") (pintype "bidirectional"))
    )
    (net (code "130") (name "unconnected-(U4B-PF10-PadH4)") (class "Default")
      (node (ref "U4") (pin "H4") (pinfunction "PF10_H4") (pintype "bidirectional"))
    )
    (net (code "131") (name "unconnected-(U4B-PF11-PadK6)") (class "Default")
      (node (ref "U4") (pin "K6") (pinfunction "PF11_K6") (pintype "bidirectional"))
    )
    (net (code "132") (name "unconnected-(U4B-PF12-PadJ6)") (class "Default")
      (node (ref "U4") (pin "J6") (pinfunction "PF12_J6") (pintype "bidirectional"))
    )
    (net (code "133") (name "unconnected-(U4B-PF13-PadM5)") (class "Default")
      (node (ref "U4") (pin "M5") (pinfunction "PF13_M5") (pintype "bidirectional"))
    )
    (net (code "134") (name "unconnected-(U4B-PG0-PadL6)") (class "Default")
      (node (ref "U4") (pin "L6") (pinfunction "PG0_L6") (pintype "bidirectional"))
    )
    (net (code "135") (name "unconnected-(U4B-PG1-PadJ7)") (class "Default")
      (node (ref "U4") (pin "J7") (pinfunction "PG1_J7") (pintype "bidirectional"))
    )
    (net (code "136") (name "unconnected-(U4B-PG2-PadH7)") (class "Default")
      (node (ref "U4") (pin "H7") (pinfunction "PG2_H7") (pintype "bidirectional"))
    )
    (net (code "137") (name "unconnected-(U4B-PG3-PadG8)") (class "Default")
      (node (ref "U4") (pin "G8") (pinfunction "PG3_G8") (pintype "bidirectional"))
    )
    (net (code "138") (name "unconnected-(U4B-PG4-PadG10)") (class "Default")
      (node (ref "U4") (pin "G10") (pinfunction "PG4_G10") (pintype "bidirectional"))
    )
    (net (code "139") (name "unconnected-(U4B-PG5-PadG9)") (class "Default")
      (node (ref "U4") (pin "G9") (pinfunction "PG5_G9") (pintype "bidirectional"))
    )
    (net (code "140") (name "unconnected-(U4B-PG6-PadG11)") (class "Default")
      (node (ref "U4") (pin "G11") (pinfunction "PG6_G11") (pintype "bidirectional"))
    )
    (net (code "141") (name "unconnected-(U4B-PG7-PadF8)") (class "Default")
      (node (ref "U4") (pin "F8") (pinfunction "PG7_F8") (pintype "bidirectional"))
    )
    (net (code "142") (name "unconnected-(U4B-PG8-PadF9)") (class "Default")
      (node (ref "U4") (pin "F9") (pinfunction "PG8_F9") (pintype "bidirectional"))
    )
    (net (code "143") (name "unconnected-(U4B-PG9-PadC7)") (class "Default")
      (node (ref "U4") (pin "C7") (pinfunction "PG9_C7") (pintype "bidirectional"))
    )
    (net (code "144") (name "unconnected-(U4B-PG10-PadD7)") (class "Default")
      (node (ref "U4") (pin "D7") (pinfunction "PG10_D7") (pintype "bidirectional"))
    )
    (net (code "145") (name "unconnected-(U4B-PG11-PadE7)") (class "Default")
      (node (ref "U4") (pin "E7") (pinfunction "PG11_E7") (pintype "bidirectional"))
    )
    (net (code "146") (name "unconnected-(U4B-PG12-PadG7)") (class "Default")
      (node (ref "U4") (pin "G7") (pinfunction "PG12_G7") (pintype "bidirectional"))
    )
    (net (code "147") (name "unconnected-(U4B-PG13-PadF7)") (class "Default")
      (node (ref "U4") (pin "F7") (pinfunction "PG13_F7") (pintype "bidirectional"))
    )
    (net (code "148") (name "unconnected-(U4B-PG14-PadE6)") (class "Default")
      (node (ref "U4") (pin "E6") (pinfunction "PG14_E6") (pintype "bidirectional"))
    )
    (net (code "149") (name "unconnected-(U4B-PG15-PadC6)") (class "Default")
      (node (ref "U4") (pin "C6") (pinfunction "PG15_C6") (pintype "bidirectional"))
    )
    (net (code "150") (name "unconnected-(U4C-VLXSMPS-PadE1)") (class "Default")
      (node (ref "U4") (pin "E1") (pinfunction "VLXSMPS_E1") (pintype "power_in+no_connect"))
    )
  )
)
